# Esquematico_V1.net
KiCad netlist of a schematic drawn in Altium Designer
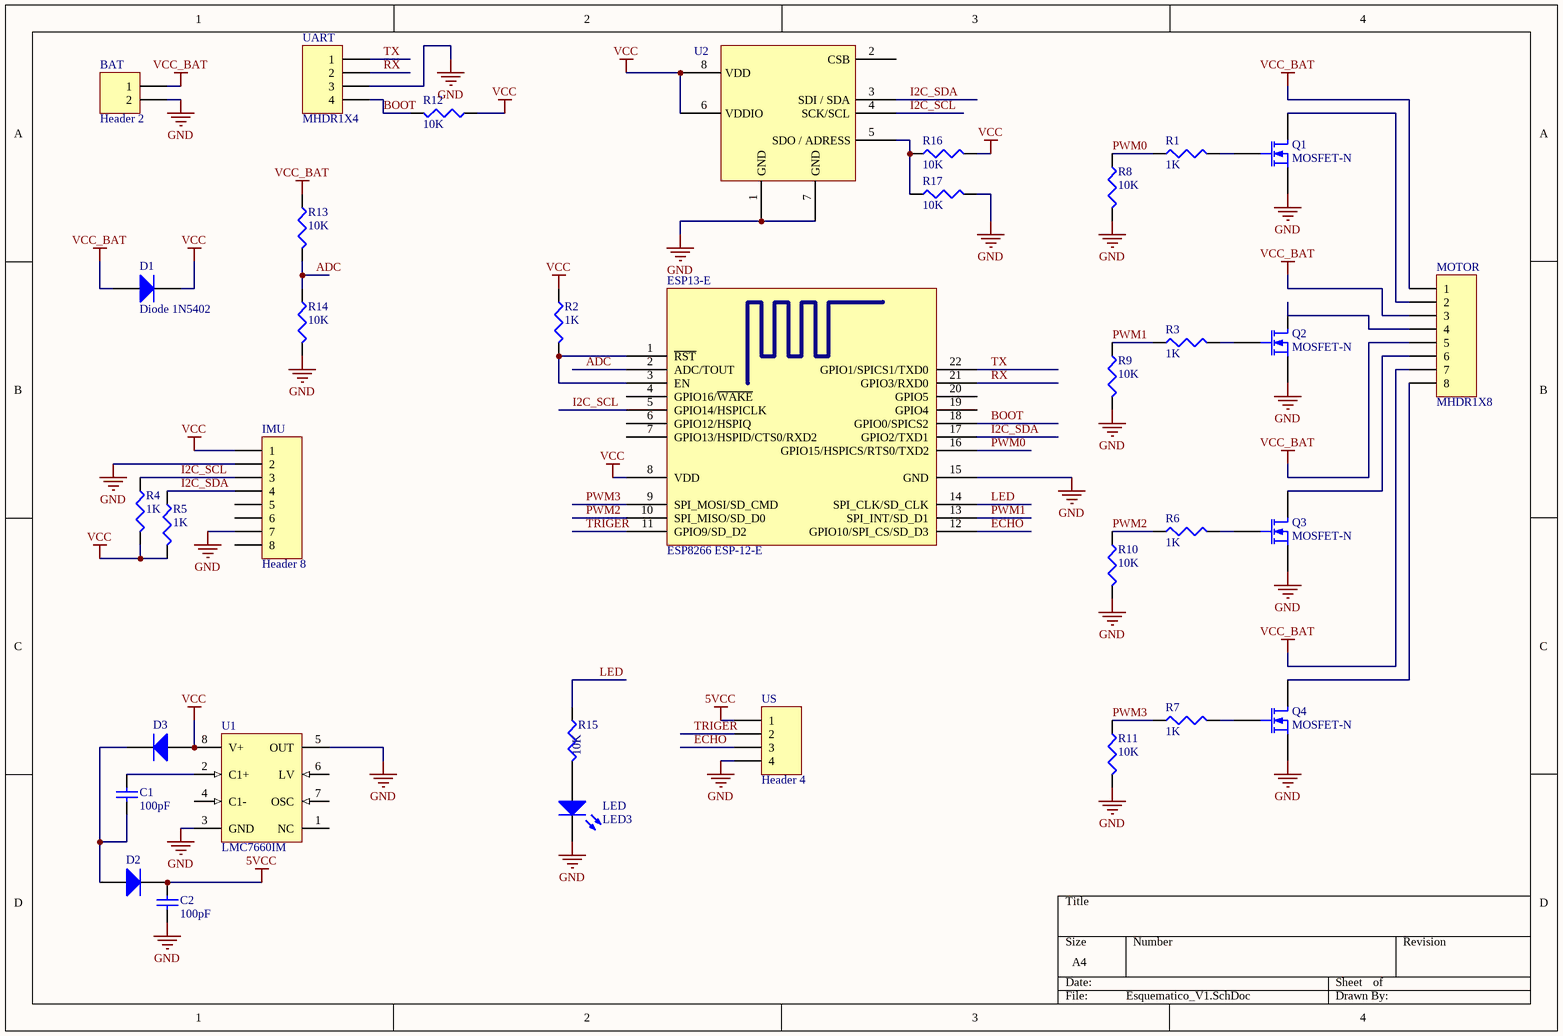
[diagram p0: Esquematico_V1.SchDoc]

(export (version "E")
  (design (tool "Eeschema 10.0.6"))
  (components
    (comp (ref "BAT")
      (value "Header 2")
      (footprint "Miscellaneous Connectors:MHDR1X2")
      (description "Header, 2-Pin")
      (fields (field (name "PUBLISHER") "Altium Limited"))
      (libsource (lib "Miscellaneous Connectors") (part "Header 2"))
    )
    (comp (ref "C1")
      (value "100pF")
      (footprint "Miscellaneous Devices:C0805")
      (description "Capacitor")
      (fields (field (name "Comment") "Cap") (field (name "PUBLISHER") "Altium Limited"))
      (libsource (lib "Miscellaneous Devices") (part "Cap"))
    )
    (comp (ref "C2")
      (value "100pF")
      (footprint "Miscellaneous Devices:C0805")
      (description "Capacitor")
      (fields (field (name "Comment") "Cap") (field (name "PUBLISHER") "Altium Limited"))
      (libsource (lib "Miscellaneous Devices") (part "Cap"))
    )
    (comp (ref "D1")
      (value "Diode 1N5402")
      (footprint "DSO-C2/X2.3")
      (description "3 Amp General Purpose Rectifier")
      (fields (field (name "PUBLISHER") "Altium Limited"))
      (libsource (lib "Miscellaneous Devices") (part "Diode 1N5402"))
    )
    (comp (ref "D2")
      (value "Diode 1N5402")
      (footprint "DSO-C2/Z6.7")
      (description "3 Amp General Purpose Rectifier")
      (fields (field (name "PUBLISHER") "Altium Limited"))
      (libsource (lib "Miscellaneous Devices") (part "Diode 1N5402"))
    )
    (comp (ref "D3")
      (value "Diode 1N5402")
      (footprint "DSO-C2/Z6.7")
      (description "3 Amp General Purpose Rectifier")
      (fields (field (name "PUBLISHER") "Altium Limited"))
      (libsource (lib "Miscellaneous Devices") (part "Diode 1N5402"))
    )
    (comp (ref "ESP13-E")
      (value "ESP8266 ESP-12-E")
      (footprint "ESP8266:ESP8266 ESP-12-E B")
      (libsource (lib "ESP8266") (part "ESP8266 ESP-12-E"))
    )
    (comp (ref "IMU")
      (value "Header 8")
      (footprint "HDR1X8")
      (description "Header, 8-Pin")
      (fields (field (name "PUBLISHER") "Altium Limited"))
      (libsource (lib "Miscellaneous Connectors") (part "Header 8"))
    )
    (comp (ref "LED")
      (value "LED3")
      (footprint "C0805")
      (description "Typical BLUE SiC LED")
      (fields (field (name "PUBLISHER") "Altium Limited"))
      (libsource (lib "Miscellaneous Devices") (part "LED3"))
    )
    (comp (ref "MOTOR")
      (value "MHDR1X8")
      (footprint "MHDR1X8")
      (description "Header, 8-Pin")
      (fields (field (name "PUBLISHER") "Altium Limited"))
      (libsource (lib "Miscellaneous Connectors") (part "MHDR1X8"))
    )
    (comp (ref "Q1")
      (value "MOSFET-N")
      (footprint "PBL - SMD Packages:SOT23-3")
      (description "N-Channel MOSFET")
      (fields (field (name "PUBLISHER") "Altium Limited"))
      (libsource (lib "Miscellaneous Devices") (part "MOSFET-N"))
    )
    (comp (ref "Q2")
      (value "MOSFET-N")
      (footprint "PBL - SMD Packages:SOT23-3")
      (description "N-Channel MOSFET")
      (fields (field (name "PUBLISHER") "Altium Limited"))
      (libsource (lib "Miscellaneous Devices") (part "MOSFET-N"))
    )
    (comp (ref "Q3")
      (value "MOSFET-N")
      (footprint "PBL - SMD Packages:SOT23-3")
      (description "N-Channel MOSFET")
      (fields (field (name "PUBLISHER") "Altium Limited"))
      (libsource (lib "Miscellaneous Devices") (part "MOSFET-N"))
    )
    (comp (ref "Q4")
      (value "MOSFET-N")
      (footprint "PBL - SMD Packages:SOT23-3")
      (description "N-Channel MOSFET")
      (fields (field (name "PUBLISHER") "Altium Limited"))
      (libsource (lib "Miscellaneous Devices") (part "MOSFET-N"))
    )
    (comp (ref "R1")
      (value "1K")
      (footprint "C0805")
      (description "Resistor")
      (fields (field (name "Comment") "Res3") (field (name "PUBLISHER") "Altium Limited"))
      (libsource (lib "Miscellaneous Devices") (part "Res3"))
    )
    (comp (ref "R2")
      (value "1K")
      (footprint "C0805")
      (description "Resistor")
      (fields (field (name "Comment") "Res3") (field (name "PUBLISHER") "Altium Limited"))
      (libsource (lib "Miscellaneous Devices") (part "Res3"))
    )
    (comp (ref "R3")
      (value "1K")
      (footprint "C0805")
      (description "Resistor")
      (fields (field (name "Comment") "Res3") (field (name "PUBLISHER") "Altium Limited"))
      (libsource (lib "Miscellaneous Devices") (part "Res3"))
    )
    (comp (ref "R4")
      (value "1K")
      (footprint "Miscellaneous Devices:C0805")
      (description "Resistor")
      (fields (field (name "Comment") "Res3") (field (name "PUBLISHER") "Altium Limited"))
      (libsource (lib "Miscellaneous Devices") (part "Res3"))
    )
    (comp (ref "R5")
      (value "1K")
      (footprint "Miscellaneous Devices:C0805")
      (description "Resistor")
      (fields (field (name "Comment") "Res3") (field (name "PUBLISHER") "Altium Limited"))
      (libsource (lib "Miscellaneous Devices") (part "Res3"))
    )
    (comp (ref "R6")
      (value "1K")
      (footprint "C0805")
      (description "Resistor")
      (fields (field (name "Comment") "Res3") (field (name "PUBLISHER") "Altium Limited"))
      (libsource (lib "Miscellaneous Devices") (part "Res3"))
    )
    (comp (ref "R7")
      (value "1K")
      (footprint "C0805")
      (description "Resistor")
      (fields (field (name "Comment") "Res3") (field (name "PUBLISHER") "Altium Limited"))
      (libsource (lib "Miscellaneous Devices") (part "Res3"))
    )
    (comp (ref "R8")
      (value "10K")
      (footprint "C0805")
      (description "Resistor")
      (fields (field (name "Comment") "Res3") (field (name "PUBLISHER") "Altium Limited"))
      (libsource (lib "Miscellaneous Devices") (part "Res3"))
    )
    (comp (ref "R9")
      (value "10K")
      (footprint "C0805")
      (description "Resistor")
      (fields (field (name "Comment") "Res3") (field (name "PUBLISHER") "Altium Limited"))
      (libsource (lib "Miscellaneous Devices") (part "Res3"))
    )
    (comp (ref "R10")
      (value "10K")
      (footprint "C0805")
      (description "Resistor")
      (fields (field (name "Comment") "Res3") (field (name "PUBLISHER") "Altium Limited"))
      (libsource (lib "Miscellaneous Devices") (part "Res3"))
    )
    (comp (ref "R11")
      (value "10K")
      (footprint "C0805")
      (description "Resistor")
      (fields (field (name "Comment") "Res3") (field (name "PUBLISHER") "Altium Limited"))
      (libsource (lib "Miscellaneous Devices") (part "Res3"))
    )
    (comp (ref "R12")
      (value "10K")
      (footprint "C0805")
      (description "Resistor")
      (fields (field (name "Comment") "Res3") (field (name "PUBLISHER") "Altium Limited"))
      (libsource (lib "Miscellaneous Devices") (part "Res3"))
    )
    (comp (ref "R13")
      (value "10K")
      (footprint "C0805")
      (description "Resistor")
      (fields (field (name "Comment") "Res3") (field (name "PUBLISHER") "Altium Limited"))
      (libsource (lib "Miscellaneous Devices") (part "Res3"))
    )
    (comp (ref "R14")
      (value "10K")
      (footprint "C0805")
      (description "Resistor")
      (fields (field (name "Comment") "Res3") (field (name "PUBLISHER") "Altium Limited"))
      (libsource (lib "Miscellaneous Devices") (part "Res3"))
    )
    (comp (ref "R15")
      (value "10K")
      (footprint "C0805")
      (description "Resistor")
      (fields (field (name "Comment") "Res3") (field (name "PUBLISHER") "Altium Limited"))
      (libsource (lib "Miscellaneous Devices") (part "Res3"))
    )
    (comp (ref "R16")
      (value "10K")
      (footprint "C0805")
      (description "Resistor")
      (fields (field (name "Comment") "Res3") (field (name "PUBLISHER") "Altium Limited"))
      (libsource (lib "Miscellaneous Devices") (part "Res3"))
    )
    (comp (ref "R17")
      (value "10K")
      (footprint "C0805")
      (description "Resistor")
      (fields (field (name "Comment") "Res3") (field (name "PUBLISHER") "Altium Limited"))
      (libsource (lib "Miscellaneous Devices") (part "Res3"))
    )
    (comp (ref "U1")
      (value "LMC7660IM")
      (footprint "M08A_N")
      (description "Switched Capacitor Voltage Converter, 8-pin Narrow SOIC")
      (fields
        (field (name "MANUFACTURER") "National Semiconductor")
        (field (name "PUBLISHER") "Altium Limited")
      )
      (libsource (lib "NSC Switch Caps") (part "LMC7660IM"))
    )
    (comp (ref "U2")
      (value "BMP280")
      (footprint "LGA-8_BMP280(Primary)")
      (description "Barometro")
      (libsource (lib "BMP280") (part "BMP280"))
    )
    (comp (ref "UART")
      (value "MHDR1X4")
      (footprint "MHDR1X4")
      (description "Header, 4-Pin")
      (fields (field (name "PUBLISHER") "Altium Limited"))
      (libsource (lib "Miscellaneous Connectors") (part "MHDR1X4"))
    )
    (comp (ref "US")
      (value "Header 4")
      (footprint "HDR1X4")
      (description "Header, 4-Pin")
      (fields (field (name "PUBLISHER") "Altium Limited"))
      (libsource (lib "Miscellaneous Connectors") (part "Header 4"))
    )
  )
  (nets
    (net (code "1") (name "/ADC") (class "Default")
      (node (ref "ESP13-E") (pin "2") (pinfunction "ADC/TOUT_2") (pintype "passive"))
      (node (ref "R13") (pin "2") (pinfunction "2_2") (pintype "passive"))
      (node (ref "R14") (pin "1") (pinfunction "1_1") (pintype "passive"))
    )
    (net (code "2") (name "/BOOT") (class "Default")
      (node (ref "ESP13-E") (pin "18") (pinfunction "GPIO0/SPICS2_18") (pintype "passive"))
      (node (ref "R12") (pin "2") (pinfunction "2_2") (pintype "passive"))
      (node (ref "UART") (pin "4") (pinfunction "4_4") (pintype "passive"))
    )
    (net (code "3") (name "/ECHO") (class "Default")
      (node (ref "ESP13-E") (pin "12") (pinfunction "GPIO10/SPI_CS/SD_D3_12") (pintype "passive"))
      (node (ref "US") (pin "3") (pinfunction "3_3") (pintype "passive"))
    )
    (net (code "4") (name "/I2C_SCL") (class "Default")
      (node (ref "ESP13-E") (pin "5") (pinfunction "GPIO14/HSPICLK_5") (pintype "passive"))
      (node (ref "IMU") (pin "3") (pinfunction "3_3") (pintype "passive"))
      (node (ref "R4") (pin "1") (pinfunction "1_1") (pintype "passive"))
      (node (ref "U2") (pin "4") (pinfunction "SCK/SCL_4") (pintype "passive"))
    )
    (net (code "5") (name "/I2C_SDA") (class "Default")
      (node (ref "ESP13-E") (pin "17") (pinfunction "GPIO2/TXD1_17") (pintype "passive"))
      (node (ref "IMU") (pin "4") (pinfunction "4_4") (pintype "passive"))
      (node (ref "R5") (pin "1") (pinfunction "1_1") (pintype "passive"))
      (node (ref "U2") (pin "3") (pinfunction "SDI_/_SDA_3") (pintype "passive"))
    )
    (net (code "6") (name "/LED") (class "Default")
      (node (ref "ESP13-E") (pin "14") (pinfunction "SPI_CLK/SD_CLK_14") (pintype "passive"))
      (node (ref "R15") (pin "1") (pinfunction "1_1") (pintype "passive"))
    )
    (net (code "7") (name "/PWM0") (class "Default")
      (node (ref "ESP13-E") (pin "16") (pinfunction "GPIO15/HSPICS/RTS0/TXD2_16") (pintype "passive"))
      (node (ref "R1") (pin "1") (pinfunction "1_1") (pintype "passive"))
      (node (ref "R8") (pin "1") (pinfunction "1_1") (pintype "passive"))
    )
    (net (code "8") (name "/PWM1") (class "Default")
      (node (ref "ESP13-E") (pin "13") (pinfunction "SPI_INT/SD_D1_13") (pintype "passive"))
      (node (ref "R3") (pin "1") (pinfunction "1_1") (pintype "passive"))
      (node (ref "R9") (pin "1") (pinfunction "1_1") (pintype "passive"))
    )
    (net (code "9") (name "/PWM2") (class "Default")
      (node (ref "ESP13-E") (pin "10") (pinfunction "SPI_MISO/SD_D0_10") (pintype "passive"))
      (node (ref "R10") (pin "1") (pinfunction "1_1") (pintype "passive"))
      (node (ref "R6") (pin "1") (pinfunction "1_1") (pintype "passive"))
    )
    (net (code "10") (name "/PWM3") (class "Default")
      (node (ref "ESP13-E") (pin "9") (pinfunction "SPI_MOSI/SD_CMD_9") (pintype "passive"))
      (node (ref "R11") (pin "1") (pinfunction "1_1") (pintype "passive"))
      (node (ref "R7") (pin "1") (pinfunction "1_1") (pintype "passive"))
    )
    (net (code "11") (name "/RX") (class "Default")
      (node (ref "ESP13-E") (pin "21") (pinfunction "GPIO3/RXD0_21") (pintype "passive"))
      (node (ref "UART") (pin "2") (pinfunction "2_2") (pintype "passive"))
    )
    (net (code "12") (name "/TRIGER") (class "Default")
      (node (ref "ESP13-E") (pin "11") (pinfunction "GPIO9/SD_D2_11") (pintype "passive"))
      (node (ref "US") (pin "2") (pinfunction "2_2") (pintype "passive"))
    )
    (net (code "13") (name "/TX") (class "Default")
      (node (ref "ESP13-E") (pin "22") (pinfunction "GPIO1/SPICS1/TXD0_22") (pintype "passive"))
      (node (ref "UART") (pin "1") (pinfunction "1_1") (pintype "passive"))
    )
    (net (code "14") (name "5VCC") (class "Default")
      (node (ref "C2") (pin "2") (pinfunction "2_2") (pintype "passive"))
      (node (ref "D2") (pin "2") (pinfunction "K_2") (pintype "passive"))
      (node (ref "US") (pin "1") (pinfunction "1_1") (pintype "passive"))
    )
    (net (code "15") (name "GND") (class "Default")
      (node (ref "BAT") (pin "2") (pinfunction "2_2") (pintype "passive"))
      (node (ref "C2") (pin "1") (pinfunction "1_1") (pintype "passive"))
      (node (ref "ESP13-E") (pin "15") (pinfunction "GND_15") (pintype "passive"))
      (node (ref "IMU") (pin "2") (pinfunction "2_2") (pintype "passive"))
      (node (ref "IMU") (pin "7") (pinfunction "7_7") (pintype "passive"))
      (node (ref "LED") (pin "2") (pinfunction "K_2") (pintype "passive"))
      (node (ref "Q1") (pin "3") (pinfunction "S_3") (pintype "passive"))
      (node (ref "Q2") (pin "3") (pinfunction "S_3") (pintype "passive"))
      (node (ref "Q3") (pin "3") (pinfunction "S_3") (pintype "passive"))
      (node (ref "Q4") (pin "3") (pinfunction "S_3") (pintype "passive"))
      (node (ref "R10") (pin "2") (pinfunction "2_2") (pintype "passive"))
      (node (ref "R11") (pin "2") (pinfunction "2_2") (pintype "passive"))
      (node (ref "R14") (pin "2") (pinfunction "2_2") (pintype "passive"))
      (node (ref "R17") (pin "2") (pinfunction "2_2") (pintype "passive"))
      (node (ref "R8") (pin "2") (pinfunction "2_2") (pintype "passive"))
      (node (ref "R9") (pin "2") (pinfunction "2_2") (pintype "passive"))
      (node (ref "U1") (pin "3") (pinfunction "GND_3") (pintype "power_in"))
      (node (ref "U1") (pin "5") (pinfunction "OUT_5") (pintype "power_in"))
      (node (ref "U2") (pin "1") (pinfunction "GND_1") (pintype "passive"))
      (node (ref "U2") (pin "7") (pinfunction "GND_7") (pintype "passive"))
      (node (ref "UART") (pin "3") (pinfunction "3_3") (pintype "passive"))
      (node (ref "US") (pin "4") (pinfunction "4_4") (pintype "passive"))
    )
    (net (code "16") (name "Net-(D2-A)") (class "Default")
      (node (ref "C1") (pin "2") (pinfunction "2_2") (pintype "passive"))
      (node (ref "D2") (pin "1") (pinfunction "A_1") (pintype "passive"))
      (node (ref "D3") (pin "2") (pinfunction "K_2") (pintype "passive"))
    )
    (net (code "17") (name "Net-(ESP13-E-EN)") (class "Default")
      (node (ref "ESP13-E") (pin "1") (pinfunction "~{RST}_1") (pintype "passive"))
      (node (ref "ESP13-E") (pin "3") (pinfunction "EN_3") (pintype "passive"))
      (node (ref "R2") (pin "2") (pinfunction "2_2") (pintype "passive"))
    )
    (net (code "18") (name "Net-(LED-A)") (class "Default")
      (node (ref "LED") (pin "1") (pinfunction "A_1") (pintype "passive"))
      (node (ref "R15") (pin "2") (pinfunction "2_2") (pintype "passive"))
    )
    (net (code "19") (name "Net-(Q1-D)") (class "Default")
      (node (ref "MOTOR") (pin "2") (pinfunction "2_2") (pintype "passive"))
      (node (ref "Q1") (pin "1") (pinfunction "D_1") (pintype "passive"))
    )
    (net (code "20") (name "Net-(Q1-G)") (class "Default")
      (node (ref "Q1") (pin "2") (pinfunction "G_2") (pintype "passive"))
      (node (ref "R1") (pin "2") (pinfunction "2_2") (pintype "passive"))
    )
    (net (code "21") (name "Net-(Q2-D)") (class "Default")
      (node (ref "MOTOR") (pin "4") (pinfunction "4_4") (pintype "passive"))
      (node (ref "Q2") (pin "1") (pinfunction "D_1") (pintype "passive"))
    )
    (net (code "22") (name "Net-(Q2-G)") (class "Default")
      (node (ref "Q2") (pin "2") (pinfunction "G_2") (pintype "passive"))
      (node (ref "R3") (pin "2") (pinfunction "2_2") (pintype "passive"))
    )
    (net (code "23") (name "Net-(Q3-D)") (class "Default")
      (node (ref "MOTOR") (pin "6") (pinfunction "6_6") (pintype "passive"))
      (node (ref "Q3") (pin "1") (pinfunction "D_1") (pintype "passive"))
    )
    (net (code "24") (name "Net-(Q3-G)") (class "Default")
      (node (ref "Q3") (pin "2") (pinfunction "G_2") (pintype "passive"))
      (node (ref "R6") (pin "2") (pinfunction "2_2") (pintype "passive"))
    )
    (net (code "25") (name "Net-(Q4-D)") (class "Default")
      (node (ref "MOTOR") (pin "8") (pinfunction "8_8") (pintype "passive"))
      (node (ref "Q4") (pin "1") (pinfunction "D_1") (pintype "passive"))
    )
    (net (code "26") (name "Net-(Q4-G)") (class "Default")
      (node (ref "Q4") (pin "2") (pinfunction "G_2") (pintype "passive"))
      (node (ref "R7") (pin "2") (pinfunction "2_2") (pintype "passive"))
    )
    (net (code "27") (name "Net-(U1-C1+)") (class "Default")
      (node (ref "C1") (pin "1") (pinfunction "1_1") (pintype "passive"))
      (node (ref "U1") (pin "2") (pinfunction "C1+_2") (pintype "input"))
    )
    (net (code "28") (name "Net-(U2-SDO_{slash}_ADRESS)") (class "Default")
      (node (ref "R16") (pin "1") (pinfunction "1_1") (pintype "passive"))
      (node (ref "R17") (pin "1") (pinfunction "1_1") (pintype "passive"))
      (node (ref "U2") (pin "5") (pinfunction "SDO_/_ADRESS_5") (pintype "passive"))
    )
    (net (code "29") (name "VCC") (class "Default")
      (node (ref "D1") (pin "2") (pinfunction "K_2") (pintype "passive"))
      (node (ref "D3") (pin "1") (pinfunction "A_1") (pintype "passive"))
      (node (ref "ESP13-E") (pin "8") (pinfunction "VDD_8") (pintype "passive"))
      (node (ref "IMU") (pin "1") (pinfunction "1_1") (pintype "passive"))
      (node (ref "R12") (pin "1") (pinfunction "1_1") (pintype "passive"))
      (node (ref "R16") (pin "2") (pinfunction "2_2") (pintype "passive"))
      (node (ref "R2") (pin "1") (pinfunction "1_1") (pintype "passive"))
      (node (ref "R4") (pin "2") (pinfunction "2_2") (pintype "passive"))
      (node (ref "R5") (pin "2") (pinfunction "2_2") (pintype "passive"))
      (node (ref "U1") (pin "8") (pinfunction "V+_8") (pintype "power_in"))
      (node (ref "U2") (pin "6") (pinfunction "VDDIO_6") (pintype "passive"))
      (node (ref "U2") (pin "8") (pinfunction "VDD_8") (pintype "passive"))
    )
    (net (code "30") (name "VCC_BAT") (class "Default")
      (node (ref "BAT") (pin "1") (pinfunction "1_1") (pintype "passive"))
      (node (ref "D1") (pin "1") (pinfunction "A_1") (pintype "passive"))
      (node (ref "MOTOR") (pin "1") (pinfunction "1_1") (pintype "passive"))
      (node (ref "MOTOR") (pin "3") (pinfunction "3_3") (pintype "passive"))
      (node (ref "MOTOR") (pin "5") (pinfunction "5_5") (pintype "passive"))
      (node (ref "MOTOR") (pin "7") (pinfunction "7_7") (pintype "passive"))
      (node (ref "R13") (pin "1") (pinfunction "1_1") (pintype "passive"))
    )
    (net (code "31") (name "unconnected-(ESP13-E-GPIO4-Pad19)") (class "Default")
      (node (ref "ESP13-E") (pin "19") (pinfunction "GPIO4_19") (pintype "passive"))
    )
    (net (code "32") (name "unconnected-(ESP13-E-GPIO5-Pad20)") (class "Default")
      (node (ref "ESP13-E") (pin "20") (pinfunction "GPIO5_20") (pintype "passive"))
    )
    (net (code "33") (name "unconnected-(ESP13-E-GPIO12{slash}HSPIQ-Pad6)") (class "Default")
      (node (ref "ESP13-E") (pin "6") (pinfunction "GPIO12/HSPIQ_6") (pintype "passive"))
    )
    (net (code "34") (name "unconnected-(ESP13-E-GPIO13{slash}HSPID{slash}CTS0{slash}RXD2-Pad7)") (class "Default")
      (node (ref "ESP13-E") (pin "7") (pinfunction "GPIO13/HSPID/CTS0/RXD2_7") (pintype "passive"))
    )
    (net (code "35") (name "unconnected-(ESP13-E-GPIO16{slash}~{WAKE}-Pad4)") (class "Default")
      (node (ref "ESP13-E") (pin "4") (pinfunction "GPIO16/~{WAKE}_4") (pintype "passive"))
    )
    (net (code "36") (name "unconnected-(IMU-Pad5)") (class "Default")
      (node (ref "IMU") (pin "5") (pinfunction "5_5") (pintype "passive"))
    )
    (net (code "37") (name "unconnected-(IMU-Pad6)") (class "Default")
      (node (ref "IMU") (pin "6") (pinfunction "6_6") (pintype "passive"))
    )
    (net (code "38") (name "unconnected-(IMU-Pad8)") (class "Default")
      (node (ref "IMU") (pin "8") (pinfunction "8_8") (pintype "passive"))
    )
    (net (code "39") (name "unconnected-(U1-C1--Pad4)") (class "Default")
      (node (ref "U1") (pin "4") (pinfunction "C1-_4") (pintype "input"))
    )
    (net (code "40") (name "unconnected-(U1-LV-Pad6)") (class "Default")
      (node (ref "U1") (pin "6") (pinfunction "LV_6") (pintype "input"))
    )
    (net (code "41") (name "unconnected-(U1-NC-Pad1)") (class "Default")
      (node (ref "U1") (pin "1") (pinfunction "NC_1") (pintype "passive"))
    )
    (net (code "42") (name "unconnected-(U1-OSC-Pad7)") (class "Default")
      (node (ref "U1") (pin "7") (pinfunction "OSC_7") (pintype "input"))
    )
    (net (code "43") (name "unconnected-(U2-CSB-Pad2)") (class "Default")
      (node (ref "U2") (pin "2") (pinfunction "CSB_2") (pintype "passive"))
    )
  )
)
